# EVENTCTRL_DSP.net
KiCad netlist of a schematic drawn in Altium Designer
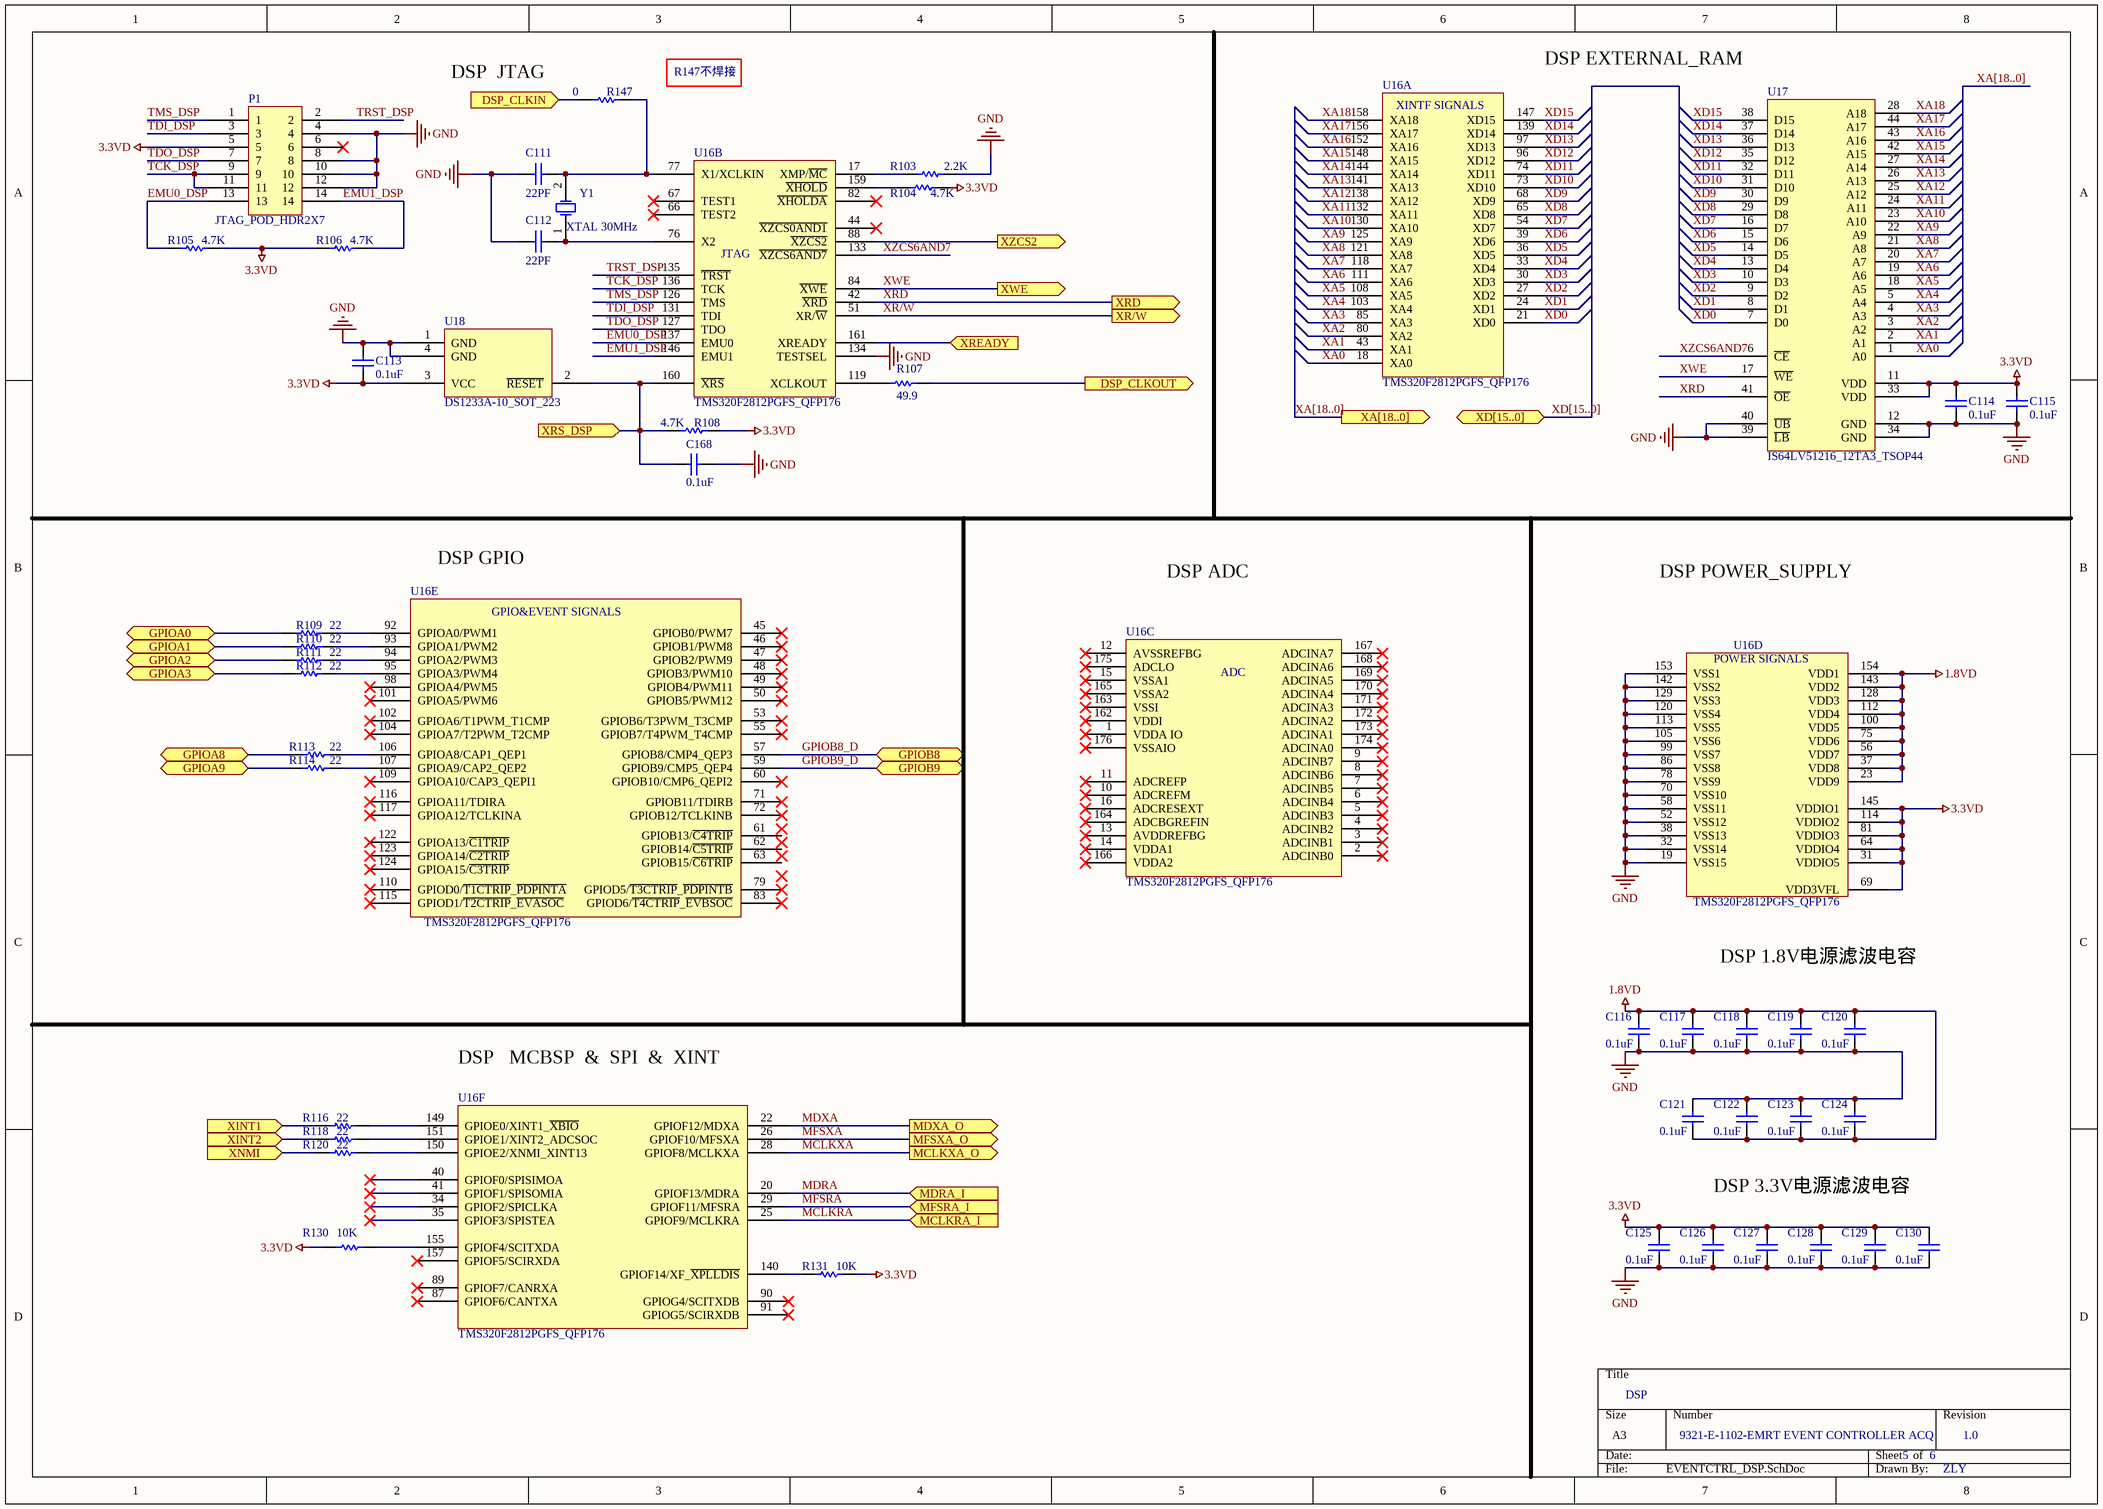
[diagram p0: EVENTCTRL_DSP.SchDoc]

(export (version "E")
  (design (tool "Eeschema 10.0.6"))
  (components
    (comp (ref "C111")
      (value "22PF")
      (footprint "0805")
      (description "Capacitor")
      (fields (field (name "Comment") "C0805"))
      (libsource (lib "Miscellaneous Devices") (part "Cap"))
    )
    (comp (ref "C112")
      (value "22PF")
      (footprint "0805")
      (description "Capacitor")
      (fields (field (name "Comment") "C0805"))
      (libsource (lib "Miscellaneous Devices") (part "Cap"))
    )
    (comp (ref "C113")
      (value "0.1uF")
      (footprint "0805")
      (description "Capacitor")
      (fields (field (name "Comment") "C0805"))
      (libsource (lib "Miscellaneous Devices") (part "Cap"))
    )
    (comp (ref "C114")
      (value "0.1uF")
      (footprint "0805")
      (description "Capacitor")
      (fields (field (name "Comment") "C0805"))
      (libsource (lib "Miscellaneous Devices") (part "Cap"))
    )
    (comp (ref "C115")
      (value "0.1uF")
      (footprint "0805")
      (description "Capacitor")
      (fields (field (name "Comment") "C0805"))
      (libsource (lib "Miscellaneous Devices") (part "Cap"))
    )
    (comp (ref "C116")
      (value "0.1uF")
      (footprint "0805")
      (description "Capacitor")
      (fields (field (name "Comment") "C0805"))
      (libsource (lib "Miscellaneous Devices") (part "Cap"))
    )
    (comp (ref "C117")
      (value "0.1uF")
      (footprint "0805")
      (description "Capacitor")
      (fields (field (name "Comment") "C0805"))
      (libsource (lib "Miscellaneous Devices") (part "Cap"))
    )
    (comp (ref "C118")
      (value "0.1uF")
      (footprint "0805")
      (description "Capacitor")
      (fields (field (name "Comment") "C0805"))
      (libsource (lib "Miscellaneous Devices") (part "Cap"))
    )
    (comp (ref "C119")
      (value "0.1uF")
      (footprint "0805")
      (description "Capacitor")
      (fields (field (name "Comment") "C0805"))
      (libsource (lib "Miscellaneous Devices") (part "Cap"))
    )
    (comp (ref "C120")
      (value "0.1uF")
      (footprint "0805")
      (description "Capacitor")
      (fields (field (name "Comment") "C0805"))
      (libsource (lib "Miscellaneous Devices") (part "Cap"))
    )
    (comp (ref "C121")
      (value "0.1uF")
      (footprint "0805")
      (description "Capacitor")
      (fields (field (name "Comment") "C0805"))
      (libsource (lib "Miscellaneous Devices") (part "Cap"))
    )
    (comp (ref "C122")
      (value "0.1uF")
      (footprint "0805")
      (description "Capacitor")
      (fields (field (name "Comment") "C0805"))
      (libsource (lib "Miscellaneous Devices") (part "Cap"))
    )
    (comp (ref "C123")
      (value "0.1uF")
      (footprint "0805")
      (description "Capacitor")
      (fields (field (name "Comment") "C0805"))
      (libsource (lib "Miscellaneous Devices") (part "Cap"))
    )
    (comp (ref "C124")
      (value "0.1uF")
      (footprint "0805")
      (description "Capacitor")
      (fields (field (name "Comment") "C0805"))
      (libsource (lib "Miscellaneous Devices") (part "Cap"))
    )
    (comp (ref "C125")
      (value "0.1uF")
      (footprint "0805")
      (description "Capacitor")
      (fields (field (name "Comment") "C0805"))
      (libsource (lib "Miscellaneous Devices") (part "Cap"))
    )
    (comp (ref "C126")
      (value "0.1uF")
      (footprint "0805")
      (description "Capacitor")
      (fields (field (name "Comment") "C0805"))
      (libsource (lib "Miscellaneous Devices") (part "Cap"))
    )
    (comp (ref "C127")
      (value "0.1uF")
      (footprint "0805")
      (description "Capacitor")
      (fields (field (name "Comment") "C0805"))
      (libsource (lib "Miscellaneous Devices") (part "Cap"))
    )
    (comp (ref "C128")
      (value "0.1uF")
      (footprint "0805")
      (description "Capacitor")
      (fields (field (name "Comment") "C0805"))
      (libsource (lib "Miscellaneous Devices") (part "Cap"))
    )
    (comp (ref "C129")
      (value "0.1uF")
      (footprint "0805")
      (description "Capacitor")
      (fields (field (name "Comment") "C0805"))
      (libsource (lib "Miscellaneous Devices") (part "Cap"))
    )
    (comp (ref "C130")
      (value "0.1uF")
      (footprint "0805")
      (description "Capacitor")
      (fields (field (name "Comment") "C0805"))
      (libsource (lib "Miscellaneous Devices") (part "Cap"))
    )
    (comp (ref "C168")
      (value "0.1uF")
      (footprint "0805")
      (description "Capacitor")
      (fields (field (name "Comment") "C0805"))
      (libsource (lib "Miscellaneous Devices") (part "Cap"))
    )
    (comp (ref "P1") (value "JTAG_POD_HDR2X7") (footprint "HDR2X7") (libsource (lib "srj") (part "JTAG_POD")))
    (comp (ref "R103")
      (value "2.2K")
      (footprint "R0805")
      (description "Resistor")
      (fields (field (name "Comment") "R0805"))
      (libsource (lib "Miscellaneous Devices") (part "Res1"))
    )
    (comp (ref "R104")
      (value "4.7K")
      (footprint "R0805")
      (description "Resistor")
      (fields (field (name "Comment") "R0805"))
      (libsource (lib "Miscellaneous Devices") (part "Res1"))
    )
    (comp (ref "R105")
      (value "4.7K")
      (footprint "R0805")
      (description "Resistor")
      (fields (field (name "Comment") "R0805"))
      (libsource (lib "Miscellaneous Devices") (part "Res1"))
    )
    (comp (ref "R106")
      (value "4.7K")
      (footprint "R0805")
      (description "Resistor")
      (fields (field (name "Comment") "R0805"))
      (libsource (lib "Miscellaneous Devices") (part "Res1"))
    )
    (comp (ref "R107")
      (value "49.9")
      (footprint "R0805")
      (description "Resistor")
      (fields (field (name "Comment") "R0805"))
      (libsource (lib "Miscellaneous Devices") (part "Res1"))
    )
    (comp (ref "R108")
      (value "4.7K")
      (footprint "R0805")
      (description "Resistor")
      (fields (field (name "Comment") "R0805"))
      (libsource (lib "Miscellaneous Devices") (part "Res1"))
    )
    (comp (ref "R109")
      (value "22")
      (footprint "R0805")
      (description "Resistor")
      (fields (field (name "Comment") "R0805") (field (name "PUBLISHER") "Altium Limited"))
      (libsource (lib "Miscellaneous Devices") (part "Res1"))
    )
    (comp (ref "R110")
      (value "22")
      (footprint "R0805")
      (description "Resistor")
      (fields (field (name "Comment") "R0805") (field (name "PUBLISHER") "Altium Limited"))
      (libsource (lib "Miscellaneous Devices") (part "Res1"))
    )
    (comp (ref "R111")
      (value "22")
      (footprint "R0805")
      (description "Resistor")
      (fields (field (name "Comment") "R0805") (field (name "PUBLISHER") "Altium Limited"))
      (libsource (lib "Miscellaneous Devices") (part "Res1"))
    )
    (comp (ref "R112")
      (value "22")
      (footprint "R0805")
      (description "Resistor")
      (fields (field (name "Comment") "R0805") (field (name "PUBLISHER") "Altium Limited"))
      (libsource (lib "Miscellaneous Devices") (part "Res1"))
    )
    (comp (ref "R113")
      (value "22")
      (footprint "R0805")
      (description "Resistor")
      (fields (field (name "Comment") "R0805"))
      (libsource (lib "Miscellaneous Devices") (part "Res1"))
    )
    (comp (ref "R114")
      (value "22")
      (footprint "R0805")
      (description "Resistor")
      (fields (field (name "Comment") "R0805"))
      (libsource (lib "Miscellaneous Devices") (part "Res1"))
    )
    (comp (ref "R116")
      (value "22")
      (footprint "R0805")
      (description "Resistor")
      (fields (field (name "Comment") "R0805"))
      (libsource (lib "Miscellaneous Devices") (part "Res1"))
    )
    (comp (ref "R118")
      (value "22")
      (footprint "R0805")
      (description "Resistor")
      (fields (field (name "Comment") "R0805"))
      (libsource (lib "Miscellaneous Devices") (part "Res1"))
    )
    (comp (ref "R120")
      (value "22")
      (footprint "R0805")
      (description "Resistor")
      (fields (field (name "Comment") "R0805"))
      (libsource (lib "Miscellaneous Devices") (part "Res1"))
    )
    (comp (ref "R130")
      (value "10K")
      (footprint "R0805")
      (description "Resistor")
      (fields (field (name "Comment") "R0805"))
      (libsource (lib "Miscellaneous Devices") (part "Res1"))
    )
    (comp (ref "R131")
      (value "10K")
      (footprint "R0805")
      (description "Resistor")
      (fields (field (name "Comment") "R0805"))
      (libsource (lib "Miscellaneous Devices") (part "Res1"))
    )
    (comp (ref "R147")
      (value "0")
      (footprint "R0805")
      (description "Resistor")
      (fields (field (name "Comment") "R0805"))
      (libsource (lib "Miscellaneous Devices") (part "Res1"))
    )
    (comp (ref "U16")
      (value "TMS320F2812PGFS_QFP176")
      (footprint "QFP176")
      (libsource (lib "srj") (part "TMS320F2812(176PIN)"))
    )
    (comp (ref "U17")
      (value "IS64LV51216_12TA3_TSOP44")
      (footprint "TSOP44")
      (libsource (lib "srj") (part "IS61LV51216"))
    )
    (comp (ref "U18")
      (value "DS1233A-10_SOT_223")
      (footprint "SOT-223")
      (libsource (lib "srj") (part "DS1233AZ-15"))
    )
    (comp (ref "Y1")
      (value "XTAL 30MHz")
      (footprint "R38")
      (description "Crystal Oscillator")
      (fields (field (name "PUBLISHER") "Altium Limited"))
      (libsource (lib "Miscellaneous Devices") (part "XTAL"))
    )
  )
  (nets
    (net (code "1") (name "/DSP_CLKIN") (class "Default")
      (node (ref "R147") (pin "2") (pinfunction "2_2") (pintype "passive"))
    )
    (net (code "2") (name "/DSP_CLKOUT") (class "Default")
      (node (ref "R107") (pin "1") (pinfunction "1_1") (pintype "passive"))
    )
    (net (code "3") (name "/EMU0_DSP") (class "Default")
      (node (ref "P1") (pin "13") (pinfunction "13_13") (pintype "passive"))
      (node (ref "R105") (pin "1") (pinfunction "1_1") (pintype "passive"))
      (node (ref "U16") (pin "137") (pinfunction "EMU0_137") (pintype "passive"))
    )
    (net (code "4") (name "/EMU1_DSP") (class "Default")
      (node (ref "P1") (pin "14") (pinfunction "14_14") (pintype "passive"))
      (node (ref "R106") (pin "2") (pinfunction "2_2") (pintype "passive"))
      (node (ref "U16") (pin "146") (pinfunction "EMU1_146") (pintype "passive"))
    )
    (net (code "5") (name "/GPIOA0") (class "Default")
      (node (ref "R109") (pin "1") (pinfunction "1_1") (pintype "passive"))
    )
    (net (code "6") (name "/GPIOA1") (class "Default")
      (node (ref "R110") (pin "1") (pinfunction "1_1") (pintype "passive"))
    )
    (net (code "7") (name "/GPIOA2") (class "Default")
      (node (ref "R111") (pin "1") (pinfunction "1_1") (pintype "passive"))
    )
    (net (code "8") (name "/GPIOA3") (class "Default")
      (node (ref "R112") (pin "1") (pinfunction "1_1") (pintype "passive"))
    )
    (net (code "9") (name "/GPIOA8") (class "Default")
      (node (ref "R113") (pin "1") (pinfunction "1_1") (pintype "passive"))
    )
    (net (code "10") (name "/GPIOA9") (class "Default")
      (node (ref "R114") (pin "1") (pinfunction "1_1") (pintype "passive"))
    )
    (net (code "11") (name "/GPIOB8_D") (class "Default")
      (node (ref "U16") (pin "57") (pinfunction "GPIOB8/CMP4_QEP3_57") (pintype "passive"))
    )
    (net (code "12") (name "/GPIOB9_D") (class "Default")
      (node (ref "U16") (pin "59") (pinfunction "GPIOB9/CMP5_QEP4_59") (pintype "passive"))
    )
    (net (code "13") (name "/MCLKRA") (class "Default")
      (node (ref "U16") (pin "25") (pinfunction "GPIOF9/MCLKRA_25") (pintype "passive"))
    )
    (net (code "14") (name "/MCLKXA") (class "Default")
      (node (ref "U16") (pin "28") (pinfunction "GPIOF8/MCLKXA_28") (pintype "passive"))
    )
    (net (code "15") (name "/MDRA") (class "Default")
      (node (ref "U16") (pin "20") (pinfunction "GPIOF13/MDRA_20") (pintype "passive"))
    )
    (net (code "16") (name "/MDXA") (class "Default")
      (node (ref "U16") (pin "22") (pinfunction "GPIOF12/MDXA_22") (pintype "passive"))
    )
    (net (code "17") (name "/MFSRA") (class "Default")
      (node (ref "U16") (pin "29") (pinfunction "GPIOF11/MFSRA_29") (pintype "passive"))
    )
    (net (code "18") (name "/MFSXA") (class "Default")
      (node (ref "U16") (pin "26") (pinfunction "GPIOF10/MFSXA_26") (pintype "passive"))
    )
    (net (code "19") (name "/TCK_DSP") (class "Default")
      (node (ref "P1") (pin "11") (pinfunction "11_11") (pintype "passive"))
      (node (ref "P1") (pin "9") (pinfunction "9_9") (pintype "passive"))
      (node (ref "U16") (pin "136") (pinfunction "TCK_136") (pintype "passive"))
    )
    (net (code "20") (name "/TDI_DSP") (class "Default")
      (node (ref "P1") (pin "3") (pinfunction "3_3") (pintype "passive"))
      (node (ref "U16") (pin "131") (pinfunction "TDI_131") (pintype "passive"))
    )
    (net (code "21") (name "/TDO_DSP") (class "Default")
      (node (ref "P1") (pin "7") (pinfunction "7_7") (pintype "passive"))
      (node (ref "U16") (pin "127") (pinfunction "TDO_127") (pintype "passive"))
    )
    (net (code "22") (name "/TMS_DSP") (class "Default")
      (node (ref "P1") (pin "1") (pinfunction "1_1") (pintype "passive"))
      (node (ref "U16") (pin "126") (pinfunction "TMS_126") (pintype "passive"))
    )
    (net (code "23") (name "/TRST_DSP") (class "Default")
      (node (ref "P1") (pin "2") (pinfunction "2_2") (pintype "passive"))
      (node (ref "U16") (pin "135") (pinfunction "~{TRST}_135") (pintype "passive"))
    )
    (net (code "24") (name "/XA0") (class "Default")
      (node (ref "U16") (pin "18") (pinfunction "XA0_18") (pintype "passive"))
      (node (ref "U17") (pin "1") (pinfunction "A0_1") (pintype "passive"))
    )
    (net (code "25") (name "/XA1") (class "Default")
      (node (ref "U16") (pin "43") (pinfunction "XA1_43") (pintype "passive"))
      (node (ref "U17") (pin "2") (pinfunction "A1_2") (pintype "passive"))
    )
    (net (code "26") (name "/XA2") (class "Default")
      (node (ref "U16") (pin "80") (pinfunction "XA2_80") (pintype "passive"))
      (node (ref "U17") (pin "3") (pinfunction "A2_3") (pintype "passive"))
    )
    (net (code "27") (name "/XA3") (class "Default")
      (node (ref "U16") (pin "85") (pinfunction "XA3_85") (pintype "passive"))
      (node (ref "U17") (pin "4") (pinfunction "A3_4") (pintype "passive"))
    )
    (net (code "28") (name "/XA4") (class "Default")
      (node (ref "U16") (pin "103") (pinfunction "XA4_103") (pintype "passive"))
      (node (ref "U17") (pin "5") (pinfunction "A4_5") (pintype "passive"))
    )
    (net (code "29") (name "/XA5") (class "Default")
      (node (ref "U16") (pin "108") (pinfunction "XA5_108") (pintype "passive"))
      (node (ref "U17") (pin "18") (pinfunction "A5_18") (pintype "passive"))
    )
    (net (code "30") (name "/XA6") (class "Default")
      (node (ref "U16") (pin "111") (pinfunction "XA6_111") (pintype "passive"))
      (node (ref "U17") (pin "19") (pinfunction "A6_19") (pintype "passive"))
    )
    (net (code "31") (name "/XA7") (class "Default")
      (node (ref "U16") (pin "118") (pinfunction "XA7_118") (pintype "passive"))
      (node (ref "U17") (pin "20") (pinfunction "A7_20") (pintype "passive"))
    )
    (net (code "32") (name "/XA8") (class "Default")
      (node (ref "U16") (pin "121") (pinfunction "XA8_121") (pintype "passive"))
      (node (ref "U17") (pin "21") (pinfunction "A8_21") (pintype "passive"))
    )
    (net (code "33") (name "/XA9") (class "Default")
      (node (ref "U16") (pin "125") (pinfunction "XA9_125") (pintype "passive"))
      (node (ref "U17") (pin "22") (pinfunction "A9_22") (pintype "passive"))
    )
    (net (code "34") (name "/XA10") (class "Default")
      (node (ref "U16") (pin "130") (pinfunction "XA10_130") (pintype "passive"))
      (node (ref "U17") (pin "23") (pinfunction "A10_23") (pintype "passive"))
    )
    (net (code "35") (name "/XA11") (class "Default")
      (node (ref "U16") (pin "132") (pinfunction "XA11_132") (pintype "passive"))
      (node (ref "U17") (pin "24") (pinfunction "A11_24") (pintype "passive"))
    )
    (net (code "36") (name "/XA12") (class "Default")
      (node (ref "U16") (pin "138") (pinfunction "XA12_138") (pintype "passive"))
      (node (ref "U17") (pin "25") (pinfunction "A12_25") (pintype "passive"))
    )
    (net (code "37") (name "/XA13") (class "Default")
      (node (ref "U16") (pin "141") (pinfunction "XA13_141") (pintype "passive"))
      (node (ref "U17") (pin "26") (pinfunction "A13_26") (pintype "passive"))
    )
    (net (code "38") (name "/XA14") (class "Default")
      (node (ref "U16") (pin "144") (pinfunction "XA14_144") (pintype "passive"))
      (node (ref "U17") (pin "27") (pinfunction "A14_27") (pintype "passive"))
    )
    (net (code "39") (name "/XA15") (class "Default")
      (node (ref "U16") (pin "148") (pinfunction "XA15_148") (pintype "passive"))
      (node (ref "U17") (pin "42") (pinfunction "A15_42") (pintype "passive"))
    )
    (net (code "40") (name "/XA16") (class "Default")
      (node (ref "U16") (pin "152") (pinfunction "XA16_152") (pintype "passive"))
      (node (ref "U17") (pin "43") (pinfunction "A16_43") (pintype "passive"))
    )
    (net (code "41") (name "/XA17") (class "Default")
      (node (ref "U16") (pin "156") (pinfunction "XA17_156") (pintype "passive"))
      (node (ref "U17") (pin "44") (pinfunction "A17_44") (pintype "passive"))
    )
    (net (code "42") (name "/XA18") (class "Default")
      (node (ref "U16") (pin "158") (pinfunction "XA18_158") (pintype "passive"))
      (node (ref "U17") (pin "28") (pinfunction "A18_28") (pintype "passive"))
    )
    (net (code "44") (name "/XD0") (class "Default")
      (node (ref "U16") (pin "21") (pinfunction "XD0_21") (pintype "passive"))
      (node (ref "U17") (pin "7") (pinfunction "D0_7") (pintype "passive"))
    )
    (net (code "45") (name "/XD1") (class "Default")
      (node (ref "U16") (pin "24") (pinfunction "XD1_24") (pintype "passive"))
      (node (ref "U17") (pin "8") (pinfunction "D1_8") (pintype "passive"))
    )
    (net (code "46") (name "/XD2") (class "Default")
      (node (ref "U16") (pin "27") (pinfunction "XD2_27") (pintype "passive"))
      (node (ref "U17") (pin "9") (pinfunction "D2_9") (pintype "passive"))
    )
    (net (code "47") (name "/XD3") (class "Default")
      (node (ref "U16") (pin "30") (pinfunction "XD3_30") (pintype "passive"))
      (node (ref "U17") (pin "10") (pinfunction "D3_10") (pintype "passive"))
    )
    (net (code "48") (name "/XD4") (class "Default")
      (node (ref "U16") (pin "33") (pinfunction "XD4_33") (pintype "passive"))
      (node (ref "U17") (pin "13") (pinfunction "D4_13") (pintype "passive"))
    )
    (net (code "49") (name "/XD5") (class "Default")
      (node (ref "U16") (pin "36") (pinfunction "XD5_36") (pintype "passive"))
      (node (ref "U17") (pin "14") (pinfunction "D5_14") (pintype "passive"))
    )
    (net (code "50") (name "/XD6") (class "Default")
      (node (ref "U16") (pin "39") (pinfunction "XD6_39") (pintype "passive"))
      (node (ref "U17") (pin "15") (pinfunction "D6_15") (pintype "passive"))
    )
    (net (code "51") (name "/XD7") (class "Default")
      (node (ref "U16") (pin "54") (pinfunction "XD7_54") (pintype "passive"))
      (node (ref "U17") (pin "16") (pinfunction "D7_16") (pintype "passive"))
    )
    (net (code "52") (name "/XD8") (class "Default")
      (node (ref "U16") (pin "65") (pinfunction "XD8_65") (pintype "passive"))
      (node (ref "U17") (pin "29") (pinfunction "D8_29") (pintype "passive"))
    )
    (net (code "53") (name "/XD9") (class "Default")
      (node (ref "U16") (pin "68") (pinfunction "XD9_68") (pintype "passive"))
      (node (ref "U17") (pin "30") (pinfunction "D9_30") (pintype "passive"))
    )
    (net (code "54") (name "/XD10") (class "Default")
      (node (ref "U16") (pin "73") (pinfunction "XD10_73") (pintype "passive"))
      (node (ref "U17") (pin "31") (pinfunction "D10_31") (pintype "passive"))
    )
    (net (code "55") (name "/XD11") (class "Default")
      (node (ref "U16") (pin "74") (pinfunction "XD11_74") (pintype "passive"))
      (node (ref "U17") (pin "32") (pinfunction "D11_32") (pintype "passive"))
    )
    (net (code "56") (name "/XD12") (class "Default")
      (node (ref "U16") (pin "96") (pinfunction "XD12_96") (pintype "passive"))
      (node (ref "U17") (pin "35") (pinfunction "D12_35") (pintype "passive"))
    )
    (net (code "57") (name "/XD13") (class "Default")
      (node (ref "U16") (pin "97") (pinfunction "XD13_97") (pintype "passive"))
      (node (ref "U17") (pin "36") (pinfunction "D13_36") (pintype "passive"))
    )
    (net (code "58") (name "/XD14") (class "Default")
      (node (ref "U16") (pin "139") (pinfunction "XD14_139") (pintype "passive"))
      (node (ref "U17") (pin "37") (pinfunction "D14_37") (pintype "passive"))
    )
    (net (code "59") (name "/XD15") (class "Default")
      (node (ref "U16") (pin "147") (pinfunction "XD15_147") (pintype "passive"))
      (node (ref "U17") (pin "38") (pinfunction "D15_38") (pintype "passive"))
    )
    (net (code "61") (name "/XINT1") (class "Default")
      (node (ref "R116") (pin "1") (pinfunction "1_1") (pintype "passive"))
    )
    (net (code "62") (name "/XINT2") (class "Default")
      (node (ref "R118") (pin "1") (pinfunction "1_1") (pintype "passive"))
    )
    (net (code "63") (name "/XNMI") (class "Default")
      (node (ref "R120") (pin "1") (pinfunction "1_1") (pintype "passive"))
    )
    (net (code "64") (name "/XRD") (class "Default")
      (node (ref "U16") (pin "42") (pinfunction "~{XRD}_42") (pintype "passive"))
      (node (ref "U17") (pin "41") (pinfunction "~{OE}_41") (pintype "passive"))
    )
    (net (code "65") (name "/XREADY") (class "Default")
      (node (ref "U16") (pin "161") (pinfunction "XREADY_161") (pintype "passive"))
    )
    (net (code "66") (name "/XRS_DSP") (class "Default")
      (node (ref "C168") (pin "1") (pinfunction "1_1") (pintype "passive"))
      (node (ref "R108") (pin "2") (pinfunction "2_2") (pintype "passive"))
      (node (ref "U16") (pin "160") (pinfunction "~{XRS}_160") (pintype "passive"))
      (node (ref "U18") (pin "2") (pinfunction "~{RESET}_2") (pintype "passive"))
    )
    (net (code "67") (name "/XR{slash}W") (class "Default")
      (node (ref "U16") (pin "51") (pinfunction "XR/~{W}_51") (pintype "passive"))
    )
    (net (code "68") (name "/XWE") (class "Default")
      (node (ref "U16") (pin "84") (pinfunction "~{XWE}_84") (pintype "passive"))
      (node (ref "U17") (pin "17") (pinfunction "~{WE}_17") (pintype "passive"))
    )
    (net (code "69") (name "/XZCS2") (class "Default")
      (node (ref "U16") (pin "88") (pinfunction "~{XZCS2}_88") (pintype "passive"))
    )
    (net (code "70") (name "/XZCS6AND7") (class "Default")
      (node (ref "U16") (pin "133") (pinfunction "~{XZCS6AND7}_133") (pintype "passive"))
      (node (ref "U17") (pin "6") (pinfunction "~{CE}_6") (pintype "passive"))
    )
    (net (code "71") (name "1.8VD") (class "Default")
      (node (ref "C116") (pin "1") (pinfunction "1_1") (pintype "passive"))
      (node (ref "C117") (pin "1") (pinfunction "1_1") (pintype "passive"))
      (node (ref "C118") (pin "1") (pinfunction "1_1") (pintype "passive"))
      (node (ref "C119") (pin "1") (pinfunction "1_1") (pintype "passive"))
      (node (ref "C120") (pin "1") (pinfunction "1_1") (pintype "passive"))
      (node (ref "C121") (pin "2") (pinfunction "2_2") (pintype "passive"))
      (node (ref "C122") (pin "2") (pinfunction "2_2") (pintype "passive"))
      (node (ref "C123") (pin "2") (pinfunction "2_2") (pintype "passive"))
      (node (ref "C124") (pin "2") (pinfunction "2_2") (pintype "passive"))
      (node (ref "U16") (pin "100") (pinfunction "VDD5_100") (pintype "passive"))
      (node (ref "U16") (pin "112") (pinfunction "VDD4_112") (pintype "passive"))
      (node (ref "U16") (pin "128") (pinfunction "VDD3_128") (pintype "passive"))
      (node (ref "U16") (pin "143") (pinfunction "VDD2_143") (pintype "passive"))
      (node (ref "U16") (pin "154") (pinfunction "VDD1_154") (pintype "passive"))
      (node (ref "U16") (pin "23") (pinfunction "VDD9_23") (pintype "passive"))
      (node (ref "U16") (pin "37") (pinfunction "VDD8_37") (pintype "passive"))
      (node (ref "U16") (pin "56") (pinfunction "VDD7_56") (pintype "passive"))
      (node (ref "U16") (pin "75") (pinfunction "VDD6_75") (pintype "passive"))
    )
    (net (code "72") (name "3.3VD") (class "Default")
      (node (ref "C113") (pin "1") (pinfunction "1_1") (pintype "passive"))
      (node (ref "C114") (pin "2") (pinfunction "2_2") (pintype "passive"))
      (node (ref "C115") (pin "2") (pinfunction "2_2") (pintype "passive"))
      (node (ref "C125") (pin "1") (pinfunction "1_1") (pintype "passive"))
      (node (ref "C126") (pin "1") (pinfunction "1_1") (pintype "passive"))
      (node (ref "C127") (pin "1") (pinfunction "1_1") (pintype "passive"))
      (node (ref "C128") (pin "1") (pinfunction "1_1") (pintype "passive"))
      (node (ref "C129") (pin "1") (pinfunction "1_1") (pintype "passive"))
      (node (ref "C130") (pin "1") (pinfunction "1_1") (pintype "passive"))
      (node (ref "P1") (pin "5") (pinfunction "5_5") (pintype "passive"))
      (node (ref "R104") (pin "1") (pinfunction "1_1") (pintype "passive"))
      (node (ref "R105") (pin "2") (pinfunction "2_2") (pintype "passive"))
      (node (ref "R106") (pin "1") (pinfunction "1_1") (pintype "passive"))
      (node (ref "R108") (pin "1") (pinfunction "1_1") (pintype "passive"))
      (node (ref "R130") (pin "1") (pinfunction "1_1") (pintype "passive"))
      (node (ref "R131") (pin "1") (pinfunction "1_1") (pintype "passive"))
      (node (ref "U16") (pin "114") (pinfunction "VDDIO2_114") (pintype "passive"))
      (node (ref "U16") (pin "145") (pinfunction "VDDIO1_145") (pintype "passive"))
      (node (ref "U16") (pin "31") (pinfunction "VDDIO5_31") (pintype "passive"))
      (node (ref "U16") (pin "64") (pinfunction "VDDIO4_64") (pintype "passive"))
      (node (ref "U16") (pin "69") (pinfunction "VDD3VFL_69") (pintype "passive"))
      (node (ref "U16") (pin "81") (pinfunction "VDDIO3_81") (pintype "passive"))
      (node (ref "U17") (pin "11") (pinfunction "VDD_11") (pintype "passive"))
      (node (ref "U17") (pin "33") (pinfunction "VDD_33") (pintype "passive"))
      (node (ref "U18") (pin "3") (pinfunction "VCC_3") (pintype "passive"))
    )
    (net (code "73") (name "GND") (class "Default")
      (node (ref "C111") (pin "1") (pinfunction "1_1") (pintype "passive"))
      (node (ref "C112") (pin "1") (pinfunction "1_1") (pintype "passive"))
      (node (ref "C113") (pin "2") (pinfunction "2_2") (pintype "passive"))
      (node (ref "C114") (pin "1") (pinfunction "1_1") (pintype "passive"))
      (node (ref "C115") (pin "1") (pinfunction "1_1") (pintype "passive"))
      (node (ref "C116") (pin "2") (pinfunction "2_2") (pintype "passive"))
      (node (ref "C117") (pin "2") (pinfunction "2_2") (pintype "passive"))
      (node (ref "C118") (pin "2") (pinfunction "2_2") (pintype "passive"))
      (node (ref "C119") (pin "2") (pinfunction "2_2") (pintype "passive"))
      (node (ref "C120") (pin "2") (pinfunction "2_2") (pintype "passive"))
      (node (ref "C121") (pin "1") (pinfunction "1_1") (pintype "passive"))
      (node (ref "C122") (pin "1") (pinfunction "1_1") (pintype "passive"))
      (node (ref "C123") (pin "1") (pinfunction "1_1") (pintype "passive"))
      (node (ref "C124") (pin "1") (pinfunction "1_1") (pintype "passive"))
      (node (ref "C125") (pin "2") (pinfunction "2_2") (pintype "passive"))
      (node (ref "C126") (pin "2") (pinfunction "2_2") (pintype "passive"))
      (node (ref "C127") (pin "2") (pinfunction "2_2") (pintype "passive"))
      (node (ref "C128") (pin "2") (pinfunction "2_2") (pintype "passive"))
      (node (ref "C129") (pin "2") (pinfunction "2_2") (pintype "passive"))
      (node (ref "C130") (pin "2") (pinfunction "2_2") (pintype "passive"))
      (node (ref "C168") (pin "2") (pinfunction "2_2") (pintype "passive"))
      (node (ref "P1") (pin "10") (pinfunction "10_10") (pintype "passive"))
      (node (ref "P1") (pin "12") (pinfunction "12_12") (pintype "passive"))
      (node (ref "P1") (pin "4") (pinfunction "4_4") (pintype "passive"))
      (node (ref "P1") (pin "8") (pinfunction "8_8") (pintype "passive"))
      (node (ref "R103") (pin "1") (pinfunction "1_1") (pintype "passive"))
      (node (ref "U16") (pin "105") (pinfunction "VSS6_105") (pintype "passive"))
      (node (ref "U16") (pin "113") (pinfunction "VSS5_113") (pintype "passive"))
      (node (ref "U16") (pin "120") (pinfunction "VSS4_120") (pintype "passive"))
      (node (ref "U16") (pin "129") (pinfunction "VSS3_129") (pintype "passive"))
      (node (ref "U16") (pin "134") (pinfunction "TESTSEL_134") (pintype "passive"))
      (node (ref "U16") (pin "142") (pinfunction "VSS2_142") (pintype "passive"))
      (node (ref "U16") (pin "153") (pinfunction "VSS1_153") (pintype "passive"))
      (node (ref "U16") (pin "19") (pinfunction "VSS15_19") (pintype "passive"))
      (node (ref "U16") (pin "32") (pinfunction "VSS14_32") (pintype "passive"))
      (node (ref "U16") (pin "38") (pinfunction "VSS13_38") (pintype "passive"))
      (node (ref "U16") (pin "52") (pinfunction "VSS12_52") (pintype "passive"))
      (node (ref "U16") (pin "58") (pinfunction "VSS11_58") (pintype "passive"))
      (node (ref "U16") (pin "70") (pinfunction "VSS10_70") (pintype "passive"))
      (node (ref "U16") (pin "78") (pinfunction "VSS9_78") (pintype "passive"))
      (node (ref "U16") (pin "86") (pinfunction "VSS8_86") (pintype "passive"))
      (node (ref "U16") (pin "99") (pinfunction "VSS7_99") (pintype "passive"))
      (node (ref "U17") (pin "12") (pinfunction "GND_12") (pintype "passive"))
      (node (ref "U17") (pin "34") (pinfunction "GND_34") (pintype "passive"))
      (node (ref "U17") (pin "39") (pinfunction "~{LB}_39") (pintype "passive"))
      (node (ref "U17") (pin "40") (pinfunction "~{UB}_40") (pintype "passive"))
      (node (ref "U18") (pin "1") (pinfunction "GND_1") (pintype "passive"))
      (node (ref "U18") (pin "4") (pinfunction "GND_4") (pintype "passive"))
    )
    (net (code "74") (name "Net-(U16B-X1{slash}XCLKIN)") (class "Default")
      (node (ref "C111") (pin "2") (pinfunction "2_2") (pintype "passive"))
      (node (ref "R147") (pin "1") (pinfunction "1_1") (pintype "passive"))
      (node (ref "U16") (pin "77") (pinfunction "X1/XCLKIN_77") (pintype "passive"))
      (node (ref "Y1") (pin "2") (pinfunction "OSC2_2") (pintype "passive"))
    )
    (net (code "75") (name "Net-(U16B-X2)") (class "Default")
      (node (ref "C112") (pin "2") (pinfunction "2_2") (pintype "passive"))
      (node (ref "U16") (pin "76") (pinfunction "X2_76") (pintype "passive"))
      (node (ref "Y1") (pin "1") (pinfunction "OSC1_1") (pintype "passive"))
    )
    (net (code "76") (name "Net-(U16B-XCLKOUT)") (class "Default")
      (node (ref "R107") (pin "2") (pinfunction "2_2") (pintype "passive"))
      (node (ref "U16") (pin "119") (pinfunction "XCLKOUT_119") (pintype "passive"))
    )
    (net (code "77") (name "Net-(U16B-XMP{slash}~{MC})") (class "Default")
      (node (ref "R103") (pin "2") (pinfunction "2_2") (pintype "passive"))
      (node (ref "U16") (pin "17") (pinfunction "XMP/~{MC}_17") (pintype "passive"))
    )
    (net (code "78") (name "Net-(U16B-~{XHOLD})") (class "Default")
      (node (ref "R104") (pin "2") (pinfunction "2_2") (pintype "passive"))
      (node (ref "U16") (pin "159") (pinfunction "~{XHOLD}_159") (pintype "passive"))
    )
    (net (code "79") (name "Net-(U16E-GPIOA0{slash}PWM1)") (class "Default")
      (node (ref "R109") (pin "2") (pinfunction "2_2") (pintype "passive"))
      (node (ref "U16") (pin "92") (pinfunction "GPIOA0/PWM1_92") (pintype "passive"))
    )
    (net (code "80") (name "Net-(U16E-GPIOA1{slash}PWM2)") (class "Default")
      (node (ref "R110") (pin "2") (pinfunction "2_2") (pintype "passive"))
      (node (ref "U16") (pin "93") (pinfunction "GPIOA1/PWM2_93") (pintype "passive"))
    )
    (net (code "81") (name "Net-(U16E-GPIOA2{slash}PWM3)") (class "Default")
      (node (ref "R111") (pin "2") (pinfunction "2_2") (pintype "passive"))
      (node (ref "U16") (pin "94") (pinfunction "GPIOA2/PWM3_94") (pintype "passive"))
    )
    (net (code "82") (name "Net-(U16E-GPIOA3{slash}PWM4)") (class "Default")
      (node (ref "R112") (pin "2") (pinfunction "2_2") (pintype "passive"))
      (node (ref "U16") (pin "95") (pinfunction "GPIOA3/PWM4_95") (pintype "passive"))
    )
    (net (code "83") (name "Net-(U16E-GPIOA8{slash}CAP1_QEP1)") (class "Default")
      (node (ref "R113") (pin "2") (pinfunction "2_2") (pintype "passive"))
      (node (ref "U16") (pin "106") (pinfunction "GPIOA8/CAP1_QEP1_106") (pintype "passive"))
    )
    (net (code "84") (name "Net-(U16E-GPIOA9{slash}CAP2_QEP2)") (class "Default")
      (node (ref "R114") (pin "2") (pinfunction "2_2") (pintype "passive"))
      (node (ref "U16") (pin "107") (pinfunction "GPIOA9/CAP2_QEP2_107") (pintype "passive"))
    )
    (net (code "85") (name "Net-(U16F-GPIOE0{slash}XINT1_~{XBIO})") (class "Default")
      (node (ref "R116") (pin "2") (pinfunction "2_2") (pintype "passive"))
      (node (ref "U16") (pin "149") (pinfunction "GPIOE0/XINT1_~{XBIO}_149") (pintype "passive"))
    )
    (net (code "86") (name "Net-(U16F-GPIOE1{slash}XINT2_ADCSOC)") (class "Default")
      (node (ref "R118") (pin "2") (pinfunction "2_2") (pintype "passive"))
      (node (ref "U16") (pin "151") (pinfunction "GPIOE1/XINT2_ADCSOC_151") (pintype "passive"))
    )
    (net (code "87") (name "Net-(U16F-GPIOE2{slash}XNMI_XINT13)") (class "Default")
      (node (ref "R120") (pin "2") (pinfunction "2_2") (pintype "passive"))
      (node (ref "U16") (pin "150") (pinfunction "GPIOE2/XNMI_XINT13_150") (pintype "passive"))
    )
    (net (code "88") (name "Net-(U16F-GPIOF4{slash}SCITXDA)") (class "Default")
      (node (ref "R130") (pin "2") (pinfunction "2_2") (pintype "passive"))
      (node (ref "U16") (pin "155") (pinfunction "GPIOF4/SCITXDA_155") (pintype "passive"))
    )
    (net (code "89") (name "Net-(U16F-GPIOF14{slash}XF_~{XPLLDIS})") (class "Default")
      (node (ref "R131") (pin "2") (pinfunction "2_2") (pintype "passive"))
      (node (ref "U16") (pin "140") (pinfunction "GPIOF14/XF_~{XPLLDIS}_140") (pintype "passive"))
    )
    (net (code "90") (name "unconnected-(P1-Pad6)") (class "Default")
      (node (ref "P1") (pin "6") (pinfunction "6_6") (pintype "passive+no_connect"))
    )
    (net (code "91") (name "unconnected-(U16B-TEST1-Pad67)") (class "Default")
      (node (ref "U16") (pin "67") (pinfunction "TEST1_67") (pintype "passive+no_connect"))
    )
    (net (code "92") (name "unconnected-(U16B-TEST2-Pad66)") (class "Default")
      (node (ref "U16") (pin "66") (pinfunction "TEST2_66") (pintype "passive+no_connect"))
    )
    (net (code "93") (name "unconnected-(U16B-~{XHOLDA}-Pad82)") (class "Default")
      (node (ref "U16") (pin "82") (pinfunction "~{XHOLDA}_82") (pintype "passive+no_connect"))
    )
    (net (code "94") (name "unconnected-(U16B-~{XZCS0AND1}-Pad44)") (class "Default")
      (node (ref "U16") (pin "44") (pinfunction "~{XZCS0AND1}_44") (pintype "passive+no_connect"))
    )
    (net (code "95") (name "unconnected-(U16C-ADCBGREFIN-Pad164)") (class "Default")
      (node (ref "U16") (pin "164") (pinfunction "ADCBGREFIN_164") (pintype "passive+no_connect"))
    )
    (net (code "96") (name "unconnected-(U16C-ADCINA0-Pad174)") (class "Default")
      (node (ref "U16") (pin "174") (pinfunction "ADCINA0_174") (pintype "passive+no_connect"))
    )
    (net (code "97") (name "unconnected-(U16C-ADCINA1-Pad173)") (class "Default")
      (node (ref "U16") (pin "173") (pinfunction "ADCINA1_173") (pintype "passive+no_connect"))
    )
    (net (code "98") (name "unconnected-(U16C-ADCINA2-Pad172)") (class "Default")
      (node (ref "U16") (pin "172") (pinfunction "ADCINA2_172") (pintype "passive+no_connect"))
    )
    (net (code "99") (name "unconnected-(U16C-ADCINA3-Pad171)") (class "Default")
      (node (ref "U16") (pin "171") (pinfunction "ADCINA3_171") (pintype "passive+no_connect"))
    )
    (net (code "100") (name "unconnected-(U16C-ADCINA4-Pad170)") (class "Default")
      (node (ref "U16") (pin "170") (pinfunction "ADCINA4_170") (pintype "passive+no_connect"))
    )
    (net (code "101") (name "unconnected-(U16C-ADCINA5-Pad169)") (class "Default")
      (node (ref "U16") (pin "169") (pinfunction "ADCINA5_169") (pintype "passive+no_connect"))
    )
    (net (code "102") (name "unconnected-(U16C-ADCINA6-Pad168)") (class "Default")
      (node (ref "U16") (pin "168") (pinfunction "ADCINA6_168") (pintype "passive+no_connect"))
    )
    (net (code "103") (name "unconnected-(U16C-ADCINA7-Pad167)") (class "Default")
      (node (ref "U16") (pin "167") (pinfunction "ADCINA7_167") (pintype "passive+no_connect"))
    )
    (net (code "104") (name "unconnected-(U16C-ADCINB0-Pad2)") (class "Default")
      (node (ref "U16") (pin "2") (pinfunction "ADCINB0_2") (pintype "passive+no_connect"))
    )
    (net (code "105") (name "unconnected-(U16C-ADCINB1-Pad3)") (class "Default")
      (node (ref "U16") (pin "3") (pinfunction "ADCINB1_3") (pintype "passive+no_connect"))
    )
    (net (code "106") (name "unconnected-(U16C-ADCINB2-Pad4)") (class "Default")
      (node (ref "U16") (pin "4") (pinfunction "ADCINB2_4") (pintype "passive+no_connect"))
    )
    (net (code "107") (name "unconnected-(U16C-ADCINB3-Pad5)") (class "Default")
      (node (ref "U16") (pin "5") (pinfunction "ADCINB3_5") (pintype "passive+no_connect"))
    )
    (net (code "108") (name "unconnected-(U16C-ADCINB4-Pad6)") (class "Default")
      (node (ref "U16") (pin "6") (pinfunction "ADCINB4_6") (pintype "passive+no_connect"))
    )
    (net (code "109") (name "unconnected-(U16C-ADCINB5-Pad7)") (class "Default")
      (node (ref "U16") (pin "7") (pinfunction "ADCINB5_7") (pintype "passive+no_connect"))
    )
    (net (code "110") (name "unconnected-(U16C-ADCINB6-Pad8)") (class "Default")
      (node (ref "U16") (pin "8") (pinfunction "ADCINB6_8") (pintype "passive+no_connect"))
    )
    (net (code "111") (name "unconnected-(U16C-ADCINB7-Pad9)") (class "Default")
      (node (ref "U16") (pin "9") (pinfunction "ADCINB7_9") (pintype "passive+no_connect"))
    )
    (net (code "112") (name "unconnected-(U16C-ADCLO-Pad175)") (class "Default")
      (node (ref "U16") (pin "175") (pinfunction "ADCLO_175") (pintype "passive+no_connect"))
    )
    (net (code "113") (name "unconnected-(U16C-ADCREFM-Pad10)") (class "Default")
      (node (ref "U16") (pin "10") (pinfunction "ADCREFM_10") (pintype "passive+no_connect"))
    )
    (net (code "114") (name "unconnected-(U16C-ADCREFP-Pad11)") (class "Default")
      (node (ref "U16") (pin "11") (pinfunction "ADCREFP_11") (pintype "passive+no_connect"))
    )
    (net (code "115") (name "unconnected-(U16C-ADCRESEXT-Pad16)") (class "Default")
      (node (ref "U16") (pin "16") (pinfunction "ADCRESEXT_16") (pintype "passive+no_connect"))
    )
    (net (code "116") (name "unconnected-(U16C-AVDDREFBG-Pad13)") (class "Default")
      (node (ref "U16") (pin "13") (pinfunction "AVDDREFBG_13") (pintype "passive+no_connect"))
    )
    (net (code "117") (name "unconnected-(U16C-AVSSREFBG-Pad12)") (class "Default")
      (node (ref "U16") (pin "12") (pinfunction "AVSSREFBG_12") (pintype "passive+no_connect"))
    )
    (net (code "118") (name "unconnected-(U16C-VDDA1-Pad14)") (class "Default")
      (node (ref "U16") (pin "14") (pinfunction "VDDA1_14") (pintype "passive+no_connect"))
    )
    (net (code "119") (name "unconnected-(U16C-VDDA2-Pad166)") (class "Default")
      (node (ref "U16") (pin "166") (pinfunction "VDDA2_166") (pintype "passive+no_connect"))
    )
    (net (code "120") (name "unconnected-(U16C-VDDA_IO-Pad1)") (class "Default")
      (node (ref "U16") (pin "1") (pinfunction "VDDA_IO_1") (pintype "power_in+no_connect"))
    )
    (net (code "121") (name "unconnected-(U16C-VDDI-Pad162)") (class "Default")
      (node (ref "U16") (pin "162") (pinfunction "VDDI_162") (pintype "passive+no_connect"))
    )
    (net (code "122") (name "unconnected-(U16C-VSSA1-Pad15)") (class "Default")
      (node (ref "U16") (pin "15") (pinfunction "VSSA1_15") (pintype "passive+no_connect"))
    )
    (net (code "123") (name "unconnected-(U16C-VSSA2-Pad165)") (class "Default")
      (node (ref "U16") (pin "165") (pinfunction "VSSA2_165") (pintype "passive+no_connect"))
    )
    (net (code "124") (name "unconnected-(U16C-VSSAIO-Pad176)") (class "Default")
      (node (ref "U16") (pin "176") (pinfunction "VSSAIO_176") (pintype "passive+no_connect"))
    )
    (net (code "125") (name "unconnected-(U16C-VSSI-Pad163)") (class "Default")
      (node (ref "U16") (pin "163") (pinfunction "VSSI_163") (pintype "passive+no_connect"))
    )
    (net (code "126") (name "unconnected-(U16E-GPIOA4{slash}PWM5-Pad98)") (class "Default")
      (node (ref "U16") (pin "98") (pinfunction "GPIOA4/PWM5_98") (pintype "passive+no_connect"))
    )
    (net (code "127") (name "unconnected-(U16E-GPIOA5{slash}PWM6-Pad101)") (class "Default")
      (node (ref "U16") (pin "101") (pinfunction "GPIOA5/PWM6_101") (pintype "passive+no_connect"))
    )
    (net (code "128") (name "unconnected-(U16E-GPIOA6{slash}T1PWM_T1CMP-Pad102)") (class "Default")
      (node (ref "U16") (pin "102") (pinfunction "GPIOA6/T1PWM_T1CMP_102") (pintype "passive+no_connect"))
    )
    (net (code "129") (name "unconnected-(U16E-GPIOA7{slash}T2PWM_T2CMP-Pad104)") (class "Default")
      (node (ref "U16") (pin "104") (pinfunction "GPIOA7/T2PWM_T2CMP_104") (pintype "passive+no_connect"))
    )
    (net (code "130") (name "unconnected-(U16E-GPIOA10{slash}CAP3_QEPI1-Pad109)") (class "Default")
      (node (ref "U16") (pin "109") (pinfunction "GPIOA10/CAP3_QEPI1_109") (pintype "passive+no_connect"))
    )
    (net (code "131") (name "unconnected-(U16E-GPIOA11{slash}TDIRA-Pad116)") (class "Default")
      (node (ref "U16") (pin "116") (pinfunction "GPIOA11/TDIRA_116") (pintype "passive+no_connect"))
    )
    (net (code "132") (name "unconnected-(U16E-GPIOA12{slash}TCLKINA-Pad117)") (class "Default")
      (node (ref "U16") (pin "117") (pinfunction "GPIOA12/TCLKINA_117") (pintype "passive+no_connect"))
    )
    (net (code "133") (name "unconnected-(U16E-GPIOA13{slash}~{C1TRIP}-Pad122)") (class "Default")
      (node (ref "U16") (pin "122") (pinfunction "GPIOA13/~{C1TRIP}_122") (pintype "passive+no_connect"))
    )
    (net (code "134") (name "unconnected-(U16E-GPIOA14{slash}~{C2TRIP}-Pad123)") (class "Default")
      (node (ref "U16") (pin "123") (pinfunction "GPIOA14/~{C2TRIP}_123") (pintype "passive+no_connect"))
    )
    (net (code "135") (name "unconnected-(U16E-GPIOA15{slash}~{C3TRIP}-Pad124)") (class "Default")
      (node (ref "U16") (pin "124") (pinfunction "GPIOA15/~{C3TRIP}_124") (pintype "passive+no_connect"))
    )
    (net (code "136") (name "unconnected-(U16E-GPIOB0{slash}PWM7-Pad45)") (class "Default")
      (node (ref "U16") (pin "45") (pinfunction "GPIOB0/PWM7_45") (pintype "passive+no_connect"))
    )
    (net (code "137") (name "unconnected-(U16E-GPIOB1{slash}PWM8-Pad46)") (class "Default")
      (node (ref "U16") (pin "46") (pinfunction "GPIOB1/PWM8_46") (pintype "passive+no_connect"))
    )
    (net (code "138") (name "unconnected-(U16E-GPIOB2{slash}PWM9-Pad47)") (class "Default")
      (node (ref "U16") (pin "47") (pinfunction "GPIOB2/PWM9_47") (pintype "passive+no_connect"))
    )
    (net (code "139") (name "unconnected-(U16E-GPIOB3{slash}PWM10-Pad48)") (class "Default")
      (node (ref "U16") (pin "48") (pinfunction "GPIOB3/PWM10_48") (pintype "passive+no_connect"))
    )
    (net (code "140") (name "unconnected-(U16E-GPIOB4{slash}PWM11-Pad49)") (class "Default")
      (node (ref "U16") (pin "49") (pinfunction "GPIOB4/PWM11_49") (pintype "passive+no_connect"))
    )
    (net (code "141") (name "unconnected-(U16E-GPIOB5{slash}PWM12-Pad50)") (class "Default")
      (node (ref "U16") (pin "50") (pinfunction "GPIOB5/PWM12_50") (pintype "passive+no_connect"))
    )
    (net (code "142") (name "unconnected-(U16E-GPIOB6{slash}T3PWM_T3CMP-Pad53)") (class "Default")
      (node (ref "U16") (pin "53") (pinfunction "GPIOB6/T3PWM_T3CMP_53") (pintype "passive+no_connect"))
    )
    (net (code "143") (name "unconnected-(U16E-GPIOB7{slash}T4PWM_T4CMP-Pad55)") (class "Default")
      (node (ref "U16") (pin "55") (pinfunction "GPIOB7/T4PWM_T4CMP_55") (pintype "passive+no_connect"))
    )
    (net (code "144") (name "unconnected-(U16E-GPIOB10{slash}CMP6_QEPI2-Pad60)") (class "Default")
      (node (ref "U16") (pin "60") (pinfunction "GPIOB10/CMP6_QEPI2_60") (pintype "passive+no_connect"))
    )
    (net (code "145") (name "unconnected-(U16E-GPIOB11{slash}TDIRB-Pad71)") (class "Default")
      (node (ref "U16") (pin "71") (pinfunction "GPIOB11/TDIRB_71") (pintype "passive+no_connect"))
    )
    (net (code "146") (name "unconnected-(U16E-GPIOB12{slash}TCLKINB-Pad72)") (class "Default")
      (node (ref "U16") (pin "72") (pinfunction "GPIOB12/TCLKINB_72") (pintype "passive+no_connect"))
    )
    (net (code "147") (name "unconnected-(U16E-GPIOB13{slash}~{C4TRIP}-Pad61)") (class "Default")
      (node (ref "U16") (pin "61") (pinfunction "GPIOB13/~{C4TRIP}_61") (pintype "passive"))
    )
    (net (code "148") (name "unconnected-(U16E-GPIOB14{slash}~{C5TRIP}-Pad62)") (class "Default")
      (node (ref "U16") (pin "62") (pinfunction "GPIOB14/~{C5TRIP}_62") (pintype "passive"))
    )
    (net (code "149") (name "unconnected-(U16E-GPIOB15{slash}~{C6TRIP}-Pad63)") (class "Default")
      (node (ref "U16") (pin "63") (pinfunction "GPIOB15/~{C6TRIP}_63") (pintype "passive"))
    )
    (net (code "150") (name "unconnected-(U16E-GPIOD0{slash}~{T1CTRIP}_~{PDPINTA}-Pad110)") (class "Default")
      (node (ref "U16") (pin "110") (pinfunction "GPIOD0/~{T1CTRIP}_~{PDPINTA}_110") (pintype "passive+no_connect"))
    )
    (net (code "151") (name "unconnected-(U16E-GPIOD1{slash}~{T2CTRIP}_~{EVASOC}-Pad115)") (class "Default")
      (node (ref "U16") (pin "115") (pinfunction "GPIOD1/~{T2CTRIP}_~{EVASOC}_115") (pintype "passive+no_connect"))
    )
    (net (code "152") (name "unconnected-(U16E-GPIOD5{slash}~{T3CTRIP}_~{PDPINTB}-Pad79)") (class "Default")
      (node (ref "U16") (pin "79") (pinfunction "GPIOD5/~{T3CTRIP}_~{PDPINTB}_79") (pintype "passive+no_connect"))
    )
    (net (code "153") (name "unconnected-(U16E-GPIOD6{slash}~{T4CTRIP}_~{EVBSOC}-Pad83)") (class "Default")
      (node (ref "U16") (pin "83") (pinfunction "GPIOD6/~{T4CTRIP}_~{EVBSOC}_83") (pintype "passive+no_connect"))
    )
    (net (code "154") (name "unconnected-(U16F-GPIOF0{slash}SPISIMOA-Pad40)") (class "Default")
      (node (ref "U16") (pin "40") (pinfunction "GPIOF0/SPISIMOA_40") (pintype "passive+no_connect"))
    )
    (net (code "155") (name "unconnected-(U16F-GPIOF1{slash}SPISOMIA-Pad41)") (class "Default")
      (node (ref "U16") (pin "41") (pinfunction "GPIOF1/SPISOMIA_41") (pintype "passive+no_connect"))
    )
    (net (code "156") (name "unconnected-(U16F-GPIOF2{slash}SPICLKA-Pad34)") (class "Default")
      (node (ref "U16") (pin "34") (pinfunction "GPIOF2/SPICLKA_34") (pintype "passive+no_connect"))
    )
    (net (code "157") (name "unconnected-(U16F-GPIOF3{slash}SPISTEA-Pad35)") (class "Default")
      (node (ref "U16") (pin "35") (pinfunction "GPIOF3/SPISTEA_35") (pintype "passive+no_connect"))
    )
    (net (code "158") (name "unconnected-(U16F-GPIOF5{slash}SCIRXDA-Pad157)") (class "Default")
      (node (ref "U16") (pin "157") (pinfunction "GPIOF5/SCIRXDA_157") (pintype "passive+no_connect"))
    )
    (net (code "159") (name "unconnected-(U16F-GPIOF6{slash}CANTXA-Pad87)") (class "Default")
      (node (ref "U16") (pin "87") (pinfunction "GPIOF6/CANTXA_87") (pintype "passive+no_connect"))
    )
    (net (code "160") (name "unconnected-(U16F-GPIOF7{slash}CANRXA-Pad89)") (class "Default")
      (node (ref "U16") (pin "89") (pinfunction "GPIOF7/CANRXA_89") (pintype "passive+no_connect"))
    )
    (net (code "161") (name "unconnected-(U16F-GPIOG4{slash}SCITXDB-Pad90)") (class "Default")
      (node (ref "U16") (pin "90") (pinfunction "GPIOG4/SCITXDB_90") (pintype "passive+no_connect"))
    )
    (net (code "162") (name "unconnected-(U16F-GPIOG5{slash}SCIRXDB-Pad91)") (class "Default")
      (node (ref "U16") (pin "91") (pinfunction "GPIOG5/SCIRXDB_91") (pintype "passive+no_connect"))
    )
  )
)
